# 3_3VDC_Powersupply.net
KiCad netlist of a schematic drawn in Altium Designer
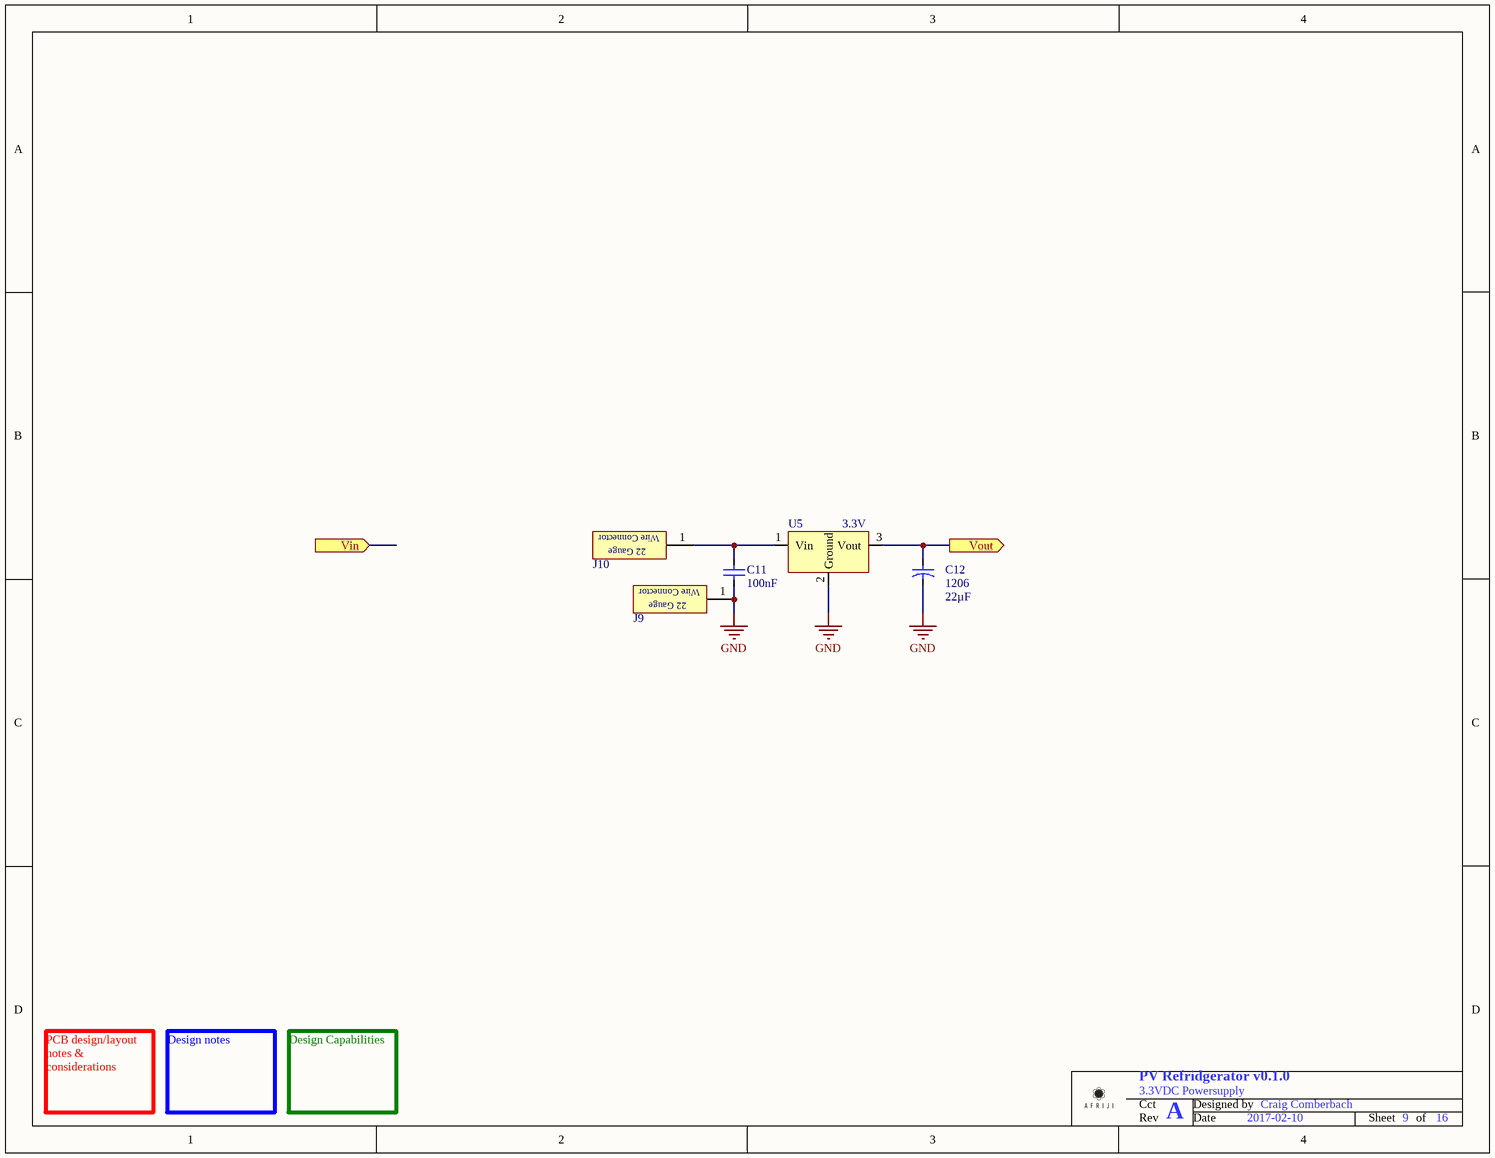
[diagram p0: 3.3VDC Powersupply.SchDoc]

(export (version "E")
  (design (tool "Eeschema 10.0.6"))
  (components
    (comp (ref "C11")
      (value "100nF 0603 50V")
      (footprint "Capacitor - 0603 Ceramic")
      (description "Non-polarized")
      (fields
        (field (name "MANUFACTURER") "Murata Electronics North America")
        (field (name "MANUFACTURER PART NUMBER") "GRM188R71H104KA93D")
        (field (name "CAPACITANCE") "100nF")
      )
      (libsource (lib "Integrated Component Library") (part "100nF 0603 50V"))
    )
    (comp (ref "C12")
      (value "1206")
      (footprint "Capacitor - 1210 Tantalum")
      (description "Polarized")
      (fields
        (field (name "MANUFACTURER") "AVX Corporation")
        (field (name "MANUFACTURER PART NUMBER") "TAJB226K010RNJ")
        (field (name "CAPACITANCE") "22µF")
      )
      (libsource (lib "Integrated Component Library") (part "22uF 1210 10V - Tantalum"))
    )
    (comp (ref "J9")
      (value "1 Pin 22-Gauge Wire connector")
      (footprint "1 Pin 22-Gauge Wire Connector")
      (libsource (lib "Personal Library") (part "1 Pin 22-Gauge Wire connector"))
    )
    (comp (ref "J10")
      (value "1 Pin 22-Gauge Wire connector")
      (footprint "1 Pin 22-Gauge Wire Connector")
      (libsource (lib "Personal Library") (part "1 Pin 22-Gauge Wire connector"))
    )
    (comp (ref "U5")
      (value "3.3V Linear Voltage Regulator LDO")
      (footprint "SOT223")
      (description "500mA")
      (fields
        (field (name "MANUFACTURER") "Micrel Inc")
        (field (name "MANUFACTURER PART NUMBER") "MIC5209-3.3YS TR")
        (field (name "VOLTAGE - OUTPUT") "3.3V")
      )
      (libsource (lib "Integrated Component Library") (part "3.3V Linear Voltage Regulator LDO"))
    )
  )
  (nets
    (net (code "2") (name "/Vout") (class "Default")
      (node (ref "C12") (pin "1") (pinfunction "1_1") (pintype "passive"))
      (node (ref "U5") (pin "3") (pinfunction "Vout_3") (pintype "passive"))
    )
    (net (code "3") (name "GND") (class "Default")
      (node (ref "C11") (pin "2") (pinfunction "2_2") (pintype "passive"))
      (node (ref "C12") (pin "2") (pinfunction "2_2") (pintype "passive"))
      (node (ref "J9") (pin "1") (pinfunction "1_1") (pintype "passive"))
      (node (ref "U5") (pin "2") (pinfunction "Ground_2") (pintype "passive"))
    )
    (net (code "4") (name "Net-(U5-Vin)") (class "Default")
      (node (ref "C11") (pin "1") (pinfunction "1_1") (pintype "passive"))
      (node (ref "J10") (pin "1") (pinfunction "1_1") (pintype "passive"))
      (node (ref "U5") (pin "1") (pinfunction "Vin_1") (pintype "passive"))
    )
  )
)
